# Netzteil_Endstufe.net
KiCad netlist of a schematic drawn in EAGLE
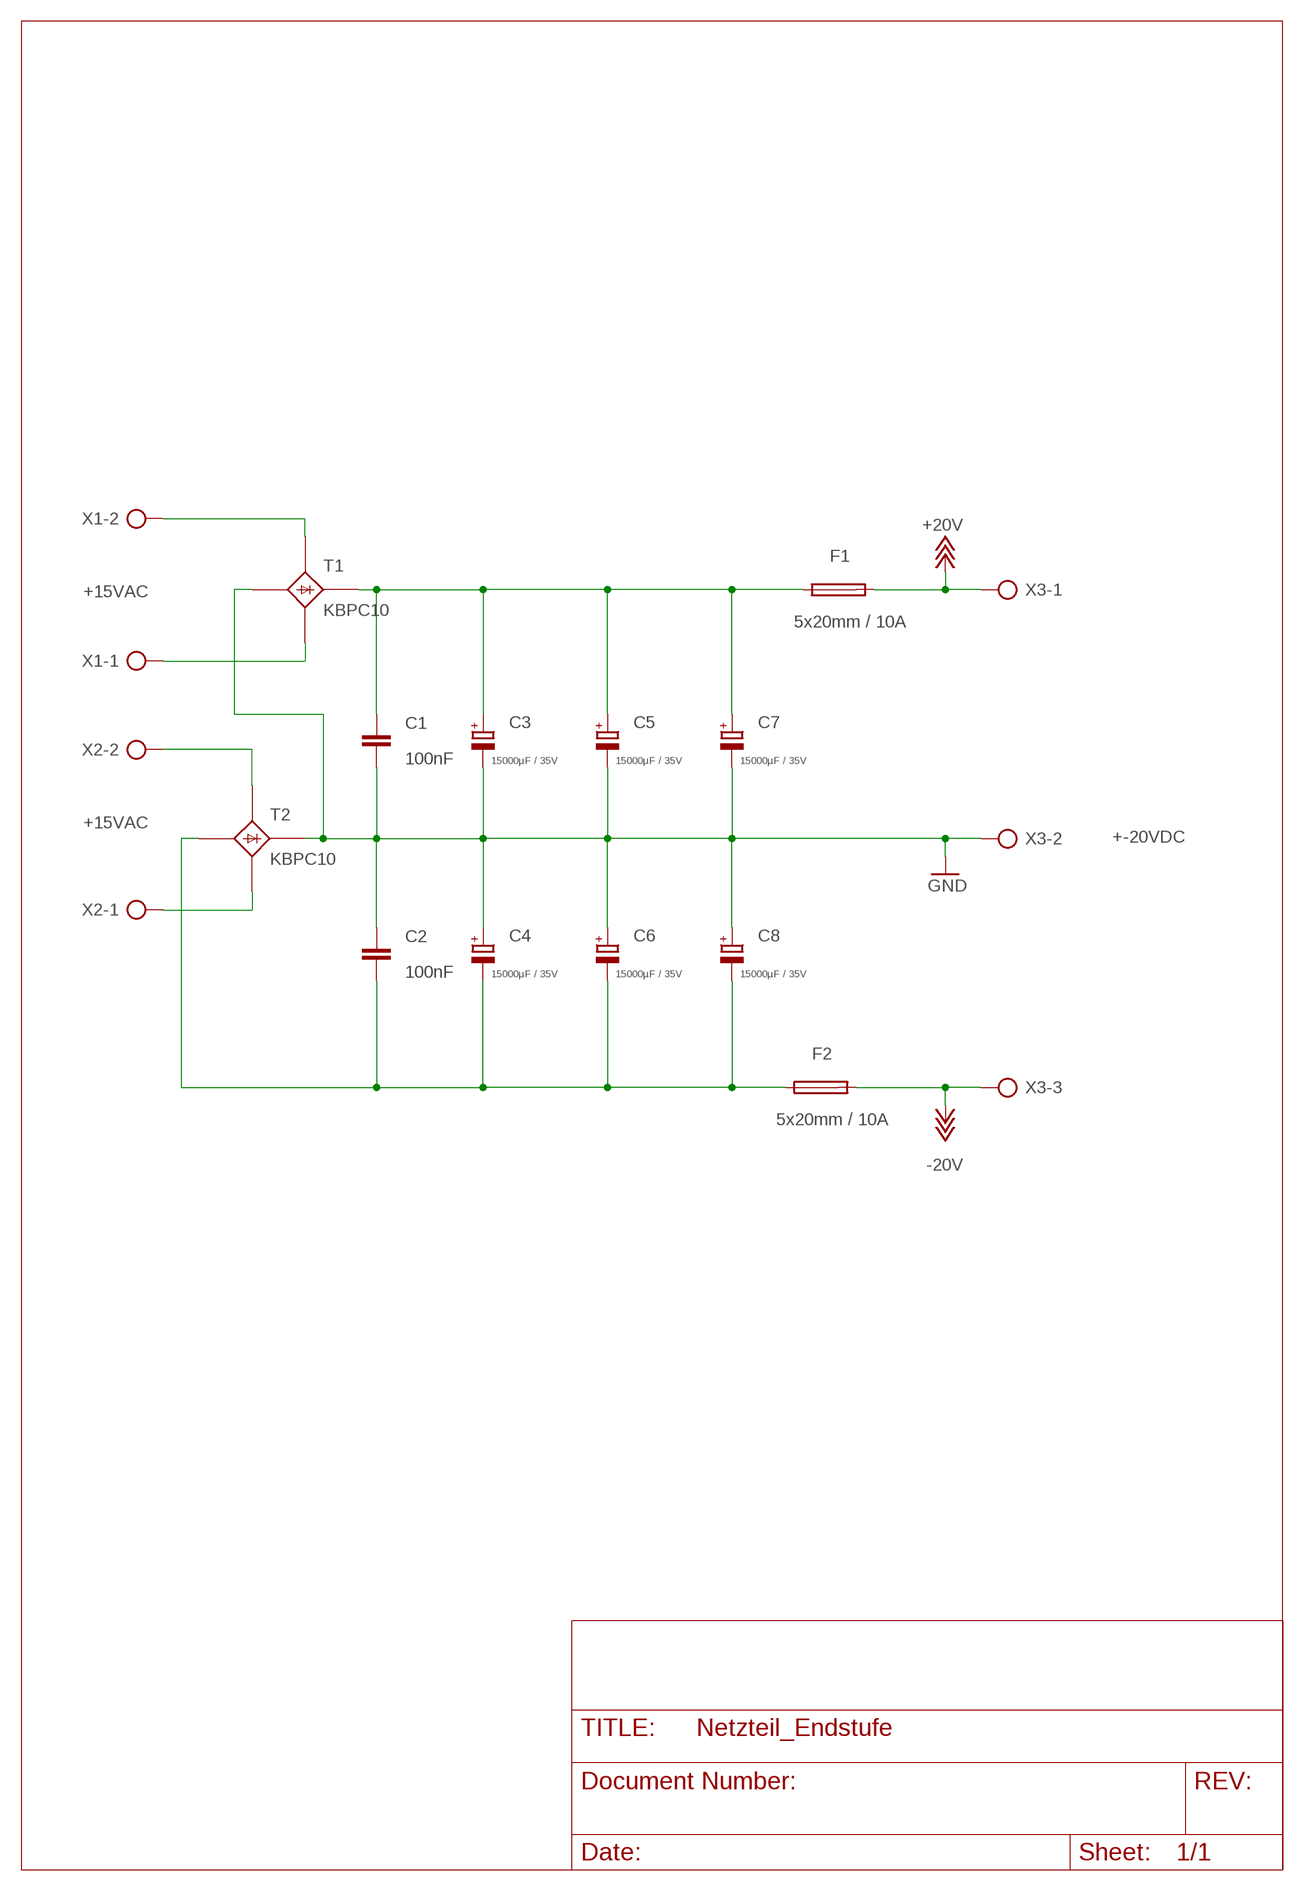
[diagram p0: schematic, sheet 1]

(export (version "E")
  (design (tool "Eeschema 10.0.6"))
  (components
    (comp (ref "C1")
      (value "100nF")
      (footprint "eagle-import:C025-025X050")
      (libsource (lib "eagle-import") (part "C-EU025-025X050"))
    )
    (comp (ref "C2")
      (value "100nF")
      (footprint "eagle-import:C025-025X050")
      (libsource (lib "eagle-import") (part "C-EU025-025X050"))
    )
    (comp (ref "C3")
      (value "15000µF / 35V")
      (footprint "eagle-import:EB22,5D")
      (libsource (lib "eagle-import") (part "CPOL-EUE10-22.5"))
    )
    (comp (ref "C4")
      (value "15000µF / 35V")
      (footprint "eagle-import:EB22,5D")
      (libsource (lib "eagle-import") (part "CPOL-EUE10-22.5"))
    )
    (comp (ref "C5")
      (value "15000µF / 35V")
      (footprint "eagle-import:EB22,5D")
      (libsource (lib "eagle-import") (part "CPOL-EUE10-22.5"))
    )
    (comp (ref "C6")
      (value "15000µF / 35V")
      (footprint "eagle-import:EB22,5D")
      (libsource (lib "eagle-import") (part "CPOL-EUE10-22.5"))
    )
    (comp (ref "C7")
      (value "15000µF / 35V")
      (footprint "eagle-import:EB22,5D")
      (libsource (lib "eagle-import") (part "CPOL-EUE10-22.5"))
    )
    (comp (ref "C8")
      (value "15000µF / 35V")
      (footprint "eagle-import:EB22,5D")
      (libsource (lib "eagle-import") (part "CPOL-EUE10-22.5"))
    )
    (comp (ref "F1")
      (value "5x20mm / 10A")
      (footprint "eagle-import:SHK20L")
      (libsource (lib "eagle-import") (part "FUSESHK20L"))
    )
    (comp (ref "F2")
      (value "5x20mm / 10A")
      (footprint "eagle-import:SHK20L")
      (libsource (lib "eagle-import") (part "FUSESHK20L"))
    )
    (comp (ref "T1")
      (value "KBPC10")
      (footprint "eagle-import:B25A-")
      (libsource (lib "eagle-import") (part "B25A-"))
    )
    (comp (ref "T2")
      (value "KBPC10")
      (footprint "eagle-import:B25A-")
      (libsource (lib "eagle-import") (part "B25A-"))
    )
    (comp (ref "X1")
      (value "+15VAC")
      (footprint "eagle-import:AK300_2")
      (libsource (lib "eagle-import") (part "AK300/2"))
    )
    (comp (ref "X2")
      (value "+15VAC")
      (footprint "eagle-import:AK300_2")
      (libsource (lib "eagle-import") (part "AK300/2"))
    )
    (comp (ref "X3")
      (value "+-20VDC")
      (footprint "eagle-import:AK300_3")
      (libsource (lib "eagle-import") (part "AK300/3"))
    )
  )
  (nets
    (net (code "1") (name "+20V") (class "Default")
      (node (ref "F1") (pin "2A") (pinfunction "2_2A") (pintype "passive"))
      (node (ref "X3") (pin "1") (pinfunction "KL_1") (pintype "passive"))
    )
    (net (code "2") (name "-20V") (class "Default")
      (node (ref "F2") (pin "2A") (pinfunction "2_2A") (pintype "passive"))
      (node (ref "X3") (pin "3") (pinfunction "KL_3") (pintype "passive"))
    )
    (net (code "3") (name "GND") (class "Default")
      (node (ref "C1") (pin "2") (pinfunction "2_2") (pintype "passive"))
      (node (ref "C2") (pin "1") (pinfunction "1_1") (pintype "passive"))
      (node (ref "C3") (pin "-") (pinfunction "-_-") (pintype "passive"))
      (node (ref "C4") (pin "+") (pinfunction "+_+") (pintype "passive"))
      (node (ref "C5") (pin "-") (pinfunction "-_-") (pintype "passive"))
      (node (ref "C6") (pin "+") (pinfunction "+_+") (pintype "passive"))
      (node (ref "C7") (pin "-") (pinfunction "-_-") (pintype "passive"))
      (node (ref "C8") (pin "+") (pinfunction "+_+") (pintype "passive"))
      (node (ref "T1") (pin "-1") (pinfunction "-_-1") (pintype "passive"))
      (node (ref "T2") (pin "+1") (pinfunction "+_+1") (pintype "passive"))
      (node (ref "X3") (pin "2") (pinfunction "KL_2") (pintype "passive"))
    )
    (net (code "4") (name "Net-(F1-1)") (class "Default")
      (node (ref "C1") (pin "1") (pinfunction "1_1") (pintype "passive"))
      (node (ref "C3") (pin "+") (pinfunction "+_+") (pintype "passive"))
      (node (ref "C5") (pin "+") (pinfunction "+_+") (pintype "passive"))
      (node (ref "C7") (pin "+") (pinfunction "+_+") (pintype "passive"))
      (node (ref "F1") (pin "1A") (pinfunction "1_1A") (pintype "passive"))
      (node (ref "T1") (pin "+1") (pinfunction "+_+1") (pintype "passive"))
    )
    (net (code "5") (name "Net-(F2-1)") (class "Default")
      (node (ref "C2") (pin "2") (pinfunction "2_2") (pintype "passive"))
      (node (ref "C4") (pin "-") (pinfunction "-_-") (pintype "passive"))
      (node (ref "C6") (pin "-") (pinfunction "-_-") (pintype "passive"))
      (node (ref "C8") (pin "-") (pinfunction "-_-") (pintype "passive"))
      (node (ref "F2") (pin "1A") (pinfunction "1_1A") (pintype "passive"))
      (node (ref "T2") (pin "-1") (pinfunction "-_-1") (pintype "passive"))
    )
    (net (code "6") (name "Net-(X1A-KL)") (class "Default")
      (node (ref "T1") (pin "AC2-") (pinfunction "AC2_AC2-") (pintype "passive"))
      (node (ref "X1") (pin "1") (pinfunction "KL_1") (pintype "passive"))
    )
    (net (code "7") (name "Net-(X1B-KL)") (class "Default")
      (node (ref "T1") (pin "AC1-") (pinfunction "AC1_AC1-") (pintype "passive"))
      (node (ref "X1") (pin "2") (pinfunction "KL_2") (pintype "passive"))
    )
    (net (code "8") (name "Net-(X2A-KL)") (class "Default")
      (node (ref "T2") (pin "AC2-") (pinfunction "AC2_AC2-") (pintype "passive"))
      (node (ref "X2") (pin "1") (pinfunction "KL_1") (pintype "passive"))
    )
    (net (code "9") (name "Net-(X2B-KL)") (class "Default")
      (node (ref "T2") (pin "AC1-") (pinfunction "AC1_AC1-") (pintype "passive"))
      (node (ref "X2") (pin "2") (pinfunction "KL_2") (pintype "passive"))
    )
    (net (code "10") (name "unconnected-(T1-Pad+)") (class "Default")
      (node (ref "T1") (pin "+") (pinfunction "+_+") (pintype "passive"))
    )
    (net (code "11") (name "unconnected-(T1-Pad-)") (class "Default")
      (node (ref "T1") (pin "-") (pinfunction "-_-") (pintype "passive"))
    )
    (net (code "12") (name "unconnected-(T1-PadAC1)") (class "Default")
      (node (ref "T1") (pin "AC1") (pinfunction "AC1_AC1") (pintype "passive"))
    )
    (net (code "13") (name "unconnected-(T1-PadAC2)") (class "Default")
      (node (ref "T1") (pin "AC2") (pinfunction "AC2_AC2") (pintype "passive"))
    )
    (net (code "14") (name "unconnected-(T2-Pad+)") (class "Default")
      (node (ref "T2") (pin "+") (pinfunction "+_+") (pintype "passive"))
    )
    (net (code "15") (name "unconnected-(T2-Pad-)") (class "Default")
      (node (ref "T2") (pin "-") (pinfunction "-_-") (pintype "passive"))
    )
    (net (code "16") (name "unconnected-(T2-PadAC1)") (class "Default")
      (node (ref "T2") (pin "AC1") (pinfunction "AC1_AC1") (pintype "passive"))
    )
    (net (code "17") (name "unconnected-(T2-PadAC2)") (class "Default")
      (node (ref "T2") (pin "AC2") (pinfunction "AC2_AC2") (pintype "passive"))
    )
  )
)
